# AFE_Shield.net
KiCad netlist of a schematic drawn in Altium Designer
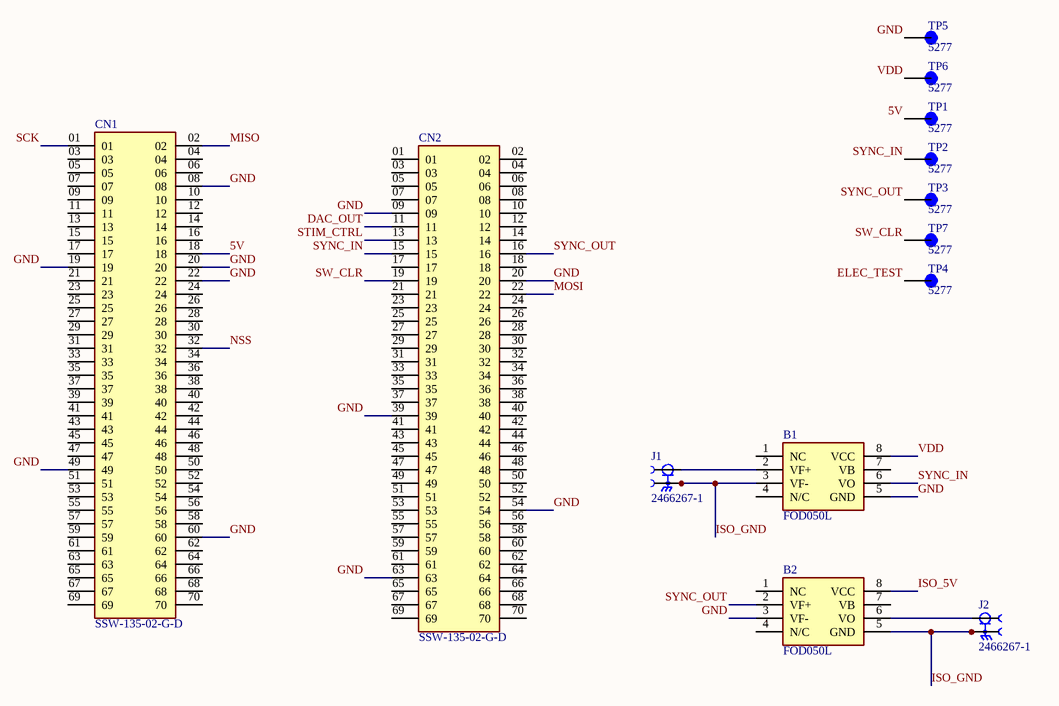
[diagram p0: AFE Shield.SchDoc]

(export (version "E")
  (design (tool "Eeschema 10.0.6"))
  (components
    (comp (ref "B1")
      (value "FOD050L")
      (footprint "SOIC127P594X363-8N")
      (fields (field (name "MOUSER PART NUMBER") "512-FOD050L"))
      (libsource (lib "James' Workspace") (part "FOD050L"))
    )
    (comp (ref "B2")
      (value "FOD050L")
      (footprint "SOIC127P594X363-8N")
      (fields (field (name "MOUSER PART NUMBER") "512-FOD050L"))
      (libsource (lib "James' Workspace") (part "FOD050L"))
    )
    (comp (ref "CN1")
      (value "SSW-135-02-G-D")
      (footprint "SAMTEC_SSW-135-02-G-D")
      (description "70-pin connector")
      (fields (field (name "MF") "Samtec"))
      (libsource (lib "James' Workspace") (part "SSW-135-02-G-D"))
    )
    (comp (ref "CN2")
      (value "SSW-135-02-G-D")
      (footprint "SAMTEC_SSW-135-02-G-D")
      (description "70-pin connector")
      (fields (field (name "MF") "Samtec"))
      (libsource (lib "James' Workspace") (part "SSW-135-02-G-D"))
    )
    (comp (ref "J1")
      (value "2466267-1")
      (footprint "TE_2466267-1")
      (description "BNC connector")
      (libsource (lib "") (part "2466267-1_1"))
    )
    (comp (ref "J2")
      (value "2466267-1")
      (footprint "TE_2466267-1")
      (description "BNC connector")
      (libsource (lib "James' Workspace") (part "2466267-1"))
    )
    (comp (ref "TP1")
      (value "5277")
      (footprint "KEYSTONE_5277")
      (description "TEST POINT (BLUE) - COMPACT")
      (fields (field (name "MF") "Keystone Electronics"))
      (libsource (lib "James' Workspace") (part "5277"))
    )
    (comp (ref "TP2")
      (value "5277")
      (footprint "KEYSTONE_5277")
      (description "TEST POINT (BLUE) - COMPACT")
      (fields (field (name "MF") "Keystone Electronics"))
      (libsource (lib "James' Workspace") (part "5277"))
    )
    (comp (ref "TP3")
      (value "5277")
      (footprint "KEYSTONE_5277")
      (description "TEST POINT (BLUE) - COMPACT")
      (fields (field (name "MF") "Keystone Electronics"))
      (libsource (lib "James' Workspace") (part "5277"))
    )
    (comp (ref "TP4")
      (value "5277")
      (footprint "KEYSTONE_5277")
      (description "TEST POINT (BLUE) - COMPACT")
      (fields (field (name "MF") "Keystone Electronics"))
      (libsource (lib "James' Workspace") (part "5277"))
    )
    (comp (ref "TP5")
      (value "5277")
      (footprint "KEYSTONE_5277")
      (description "TEST POINT (BLUE) - COMPACT")
      (fields (field (name "MF") "Keystone Electronics"))
      (libsource (lib "James' Workspace") (part "5277"))
    )
    (comp (ref "TP6")
      (value "5277")
      (footprint "KEYSTONE_5277")
      (description "TEST POINT (BLUE) - COMPACT")
      (fields (field (name "MF") "Keystone Electronics"))
      (libsource (lib "James' Workspace") (part "5277"))
    )
    (comp (ref "TP7")
      (value "5277")
      (footprint "KEYSTONE_5277")
      (description "TEST POINT (BLUE) - COMPACT")
      (fields (field (name "MF") "Keystone Electronics"))
      (libsource (lib "James' Workspace") (part "5277"))
    )
  )
  (nets
    (net (code "1") (name "/5V") (class "Default")
      (node (ref "CN1") (pin "18") (pinfunction "18_18") (pintype "passive"))
      (node (ref "TP1") (pin "1") (pinfunction "TP_1") (pintype "passive"))
    )
    (net (code "2") (name "/DAC_OUT") (class "Default")
      (node (ref "CN2") (pin "11") (pinfunction "11_11") (pintype "passive"))
    )
    (net (code "3") (name "/ELEC_TEST") (class "Default")
      (node (ref "TP4") (pin "1") (pinfunction "TP_1") (pintype "passive"))
    )
    (net (code "4") (name "/GND") (class "Default")
      (node (ref "B1") (pin "5") (pinfunction "GND_5") (pintype "passive"))
      (node (ref "B2") (pin "3") (pinfunction "VF-_3") (pintype "passive"))
      (node (ref "CN1") (pin "08") (pinfunction "08_08") (pintype "passive"))
      (node (ref "CN1") (pin "19") (pinfunction "19_19") (pintype "passive"))
      (node (ref "CN1") (pin "20") (pinfunction "20_20") (pintype "passive"))
      (node (ref "CN1") (pin "22") (pinfunction "22_22") (pintype "passive"))
      (node (ref "CN1") (pin "49") (pinfunction "49_49") (pintype "passive"))
      (node (ref "CN1") (pin "60") (pinfunction "60_60") (pintype "passive"))
      (node (ref "CN2") (pin "09") (pinfunction "09_09") (pintype "passive"))
      (node (ref "CN2") (pin "20") (pinfunction "20_20") (pintype "passive"))
      (node (ref "CN2") (pin "39") (pinfunction "39_39") (pintype "passive"))
      (node (ref "CN2") (pin "54") (pinfunction "54_54") (pintype "passive"))
      (node (ref "CN2") (pin "63") (pinfunction "63_63") (pintype "passive"))
      (node (ref "TP5") (pin "1") (pinfunction "TP_1") (pintype "passive"))
    )
    (net (code "5") (name "/ISO_5V") (class "Default")
      (node (ref "B2") (pin "8") (pinfunction "VCC_8") (pintype "passive"))
    )
    (net (code "6") (name "/ISO_GND") (class "Default")
      (node (ref "B1") (pin "3") (pinfunction "VF-_3") (pintype "passive"))
      (node (ref "B2") (pin "5") (pinfunction "GND_5") (pintype "passive"))
      (node (ref "J1") (pin "2") (pinfunction "SH_2") (pintype "power_in"))
      (node (ref "J1") (pin "3") (pinfunction "SH_3") (pintype "power_in"))
      (node (ref "J1") (pin "4") (pinfunction "SH_4") (pintype "power_in"))
      (node (ref "J1") (pin "5") (pinfunction "SH_5") (pintype "power_in"))
      (node (ref "J2") (pin "2") (pinfunction "SH_2") (pintype "power_in"))
      (node (ref "J2") (pin "3") (pinfunction "SH_3") (pintype "power_in"))
      (node (ref "J2") (pin "4") (pinfunction "SH_4") (pintype "power_in"))
      (node (ref "J2") (pin "5") (pinfunction "SH_5") (pintype "power_in"))
    )
    (net (code "7") (name "/MISO") (class "Default")
      (node (ref "CN1") (pin "02") (pinfunction "02_02") (pintype "passive"))
    )
    (net (code "8") (name "/MOSI") (class "Default")
      (node (ref "CN2") (pin "22") (pinfunction "22_22") (pintype "passive"))
    )
    (net (code "9") (name "/NSS") (class "Default")
      (node (ref "CN1") (pin "32") (pinfunction "32_32") (pintype "passive"))
    )
    (net (code "10") (name "/SCK") (class "Default")
      (node (ref "CN1") (pin "01") (pinfunction "01_01") (pintype "passive"))
    )
    (net (code "11") (name "/STIM_CTRL") (class "Default")
      (node (ref "CN2") (pin "13") (pinfunction "13_13") (pintype "passive"))
    )
    (net (code "12") (name "/SW_CLR") (class "Default")
      (node (ref "CN2") (pin "19") (pinfunction "19_19") (pintype "passive"))
      (node (ref "TP7") (pin "1") (pinfunction "TP_1") (pintype "passive"))
    )
    (net (code "13") (name "/SYNC_IN") (class "Default")
      (node (ref "B1") (pin "6") (pinfunction "VO_6") (pintype "passive"))
      (node (ref "CN2") (pin "15") (pinfunction "15_15") (pintype "passive"))
      (node (ref "TP2") (pin "1") (pinfunction "TP_1") (pintype "passive"))
    )
    (net (code "14") (name "/SYNC_OUT") (class "Default")
      (node (ref "B2") (pin "2") (pinfunction "VF+_2") (pintype "passive"))
      (node (ref "CN2") (pin "16") (pinfunction "16_16") (pintype "passive"))
      (node (ref "TP3") (pin "1") (pinfunction "TP_1") (pintype "passive"))
    )
    (net (code "15") (name "/VDD") (class "Default")
      (node (ref "B1") (pin "8") (pinfunction "VCC_8") (pintype "passive"))
      (node (ref "TP6") (pin "1") (pinfunction "TP_1") (pintype "passive"))
    )
    (net (code "16") (name "Net-(B1-VF+)") (class "Default")
      (node (ref "B1") (pin "2") (pinfunction "VF+_2") (pintype "passive"))
      (node (ref "J1") (pin "1") (pinfunction "SIG_1") (pintype "passive"))
    )
    (net (code "17") (name "Net-(B2-VO)") (class "Default")
      (node (ref "B2") (pin "6") (pinfunction "VO_6") (pintype "passive"))
      (node (ref "J2") (pin "1") (pinfunction "SIG_1") (pintype "passive"))
    )
    (net (code "18") (name "unconnected-(B1-NC-Pad1)") (class "Default")
      (node (ref "B1") (pin "1") (pinfunction "NC_1") (pintype "passive"))
    )
    (net (code "19") (name "unconnected-(B1-N{slash}C-Pad4)") (class "Default")
      (node (ref "B1") (pin "4") (pinfunction "N/C_4") (pintype "passive"))
    )
    (net (code "20") (name "unconnected-(B1-VB-Pad7)") (class "Default")
      (node (ref "B1") (pin "7") (pinfunction "VB_7") (pintype "passive"))
    )
    (net (code "21") (name "unconnected-(B2-NC-Pad1)") (class "Default")
      (node (ref "B2") (pin "1") (pinfunction "NC_1") (pintype "passive"))
    )
    (net (code "22") (name "unconnected-(B2-N{slash}C-Pad4)") (class "Default")
      (node (ref "B2") (pin "4") (pinfunction "N/C_4") (pintype "passive"))
    )
    (net (code "23") (name "unconnected-(B2-VB-Pad7)") (class "Default")
      (node (ref "B2") (pin "7") (pinfunction "VB_7") (pintype "passive"))
    )
    (net (code "24") (name "unconnected-(CN1-Pad03)") (class "Default")
      (node (ref "CN1") (pin "03") (pinfunction "03_03") (pintype "passive"))
    )
    (net (code "25") (name "unconnected-(CN1-Pad04)") (class "Default")
      (node (ref "CN1") (pin "04") (pinfunction "04_04") (pintype "passive"))
    )
    (net (code "26") (name "unconnected-(CN1-Pad05)") (class "Default")
      (node (ref "CN1") (pin "05") (pinfunction "05_05") (pintype "passive"))
    )
    (net (code "27") (name "unconnected-(CN1-Pad06)") (class "Default")
      (node (ref "CN1") (pin "06") (pinfunction "06_06") (pintype "passive"))
    )
    (net (code "28") (name "unconnected-(CN1-Pad07)") (class "Default")
      (node (ref "CN1") (pin "07") (pinfunction "07_07") (pintype "passive"))
    )
    (net (code "29") (name "unconnected-(CN1-Pad09)") (class "Default")
      (node (ref "CN1") (pin "09") (pinfunction "09_09") (pintype "passive"))
    )
    (net (code "30") (name "unconnected-(CN1-Pad10)") (class "Default")
      (node (ref "CN1") (pin "10") (pinfunction "10_10") (pintype "passive"))
    )
    (net (code "31") (name "unconnected-(CN1-Pad11)") (class "Default")
      (node (ref "CN1") (pin "11") (pinfunction "11_11") (pintype "passive"))
    )
    (net (code "32") (name "unconnected-(CN1-Pad12)") (class "Default")
      (node (ref "CN1") (pin "12") (pinfunction "12_12") (pintype "passive"))
    )
    (net (code "33") (name "unconnected-(CN1-Pad13)") (class "Default")
      (node (ref "CN1") (pin "13") (pinfunction "13_13") (pintype "passive"))
    )
    (net (code "34") (name "unconnected-(CN1-Pad14)") (class "Default")
      (node (ref "CN1") (pin "14") (pinfunction "14_14") (pintype "passive"))
    )
    (net (code "35") (name "unconnected-(CN1-Pad15)") (class "Default")
      (node (ref "CN1") (pin "15") (pinfunction "15_15") (pintype "passive"))
    )
    (net (code "36") (name "unconnected-(CN1-Pad16)") (class "Default")
      (node (ref "CN1") (pin "16") (pinfunction "16_16") (pintype "passive"))
    )
    (net (code "37") (name "unconnected-(CN1-Pad17)") (class "Default")
      (node (ref "CN1") (pin "17") (pinfunction "17_17") (pintype "passive"))
    )
    (net (code "38") (name "unconnected-(CN1-Pad21)") (class "Default")
      (node (ref "CN1") (pin "21") (pinfunction "21_21") (pintype "passive"))
    )
    (net (code "39") (name "unconnected-(CN1-Pad23)") (class "Default")
      (node (ref "CN1") (pin "23") (pinfunction "23_23") (pintype "passive"))
    )
    (net (code "40") (name "unconnected-(CN1-Pad24)") (class "Default")
      (node (ref "CN1") (pin "24") (pinfunction "24_24") (pintype "passive"))
    )
    (net (code "41") (name "unconnected-(CN1-Pad25)") (class "Default")
      (node (ref "CN1") (pin "25") (pinfunction "25_25") (pintype "passive"))
    )
    (net (code "42") (name "unconnected-(CN1-Pad26)") (class "Default")
      (node (ref "CN1") (pin "26") (pinfunction "26_26") (pintype "passive"))
    )
    (net (code "43") (name "unconnected-(CN1-Pad27)") (class "Default")
      (node (ref "CN1") (pin "27") (pinfunction "27_27") (pintype "passive"))
    )
    (net (code "44") (name "unconnected-(CN1-Pad28)") (class "Default")
      (node (ref "CN1") (pin "28") (pinfunction "28_28") (pintype "passive"))
    )
    (net (code "45") (name "unconnected-(CN1-Pad29)") (class "Default")
      (node (ref "CN1") (pin "29") (pinfunction "29_29") (pintype "passive"))
    )
    (net (code "46") (name "unconnected-(CN1-Pad30)") (class "Default")
      (node (ref "CN1") (pin "30") (pinfunction "30_30") (pintype "passive"))
    )
    (net (code "47") (name "unconnected-(CN1-Pad31)") (class "Default")
      (node (ref "CN1") (pin "31") (pinfunction "31_31") (pintype "passive"))
    )
    (net (code "48") (name "unconnected-(CN1-Pad33)") (class "Default")
      (node (ref "CN1") (pin "33") (pinfunction "33_33") (pintype "passive"))
    )
    (net (code "49") (name "unconnected-(CN1-Pad34)") (class "Default")
      (node (ref "CN1") (pin "34") (pinfunction "34_34") (pintype "passive"))
    )
    (net (code "50") (name "unconnected-(CN1-Pad35)") (class "Default")
      (node (ref "CN1") (pin "35") (pinfunction "35_35") (pintype "passive"))
    )
    (net (code "51") (name "unconnected-(CN1-Pad36)") (class "Default")
      (node (ref "CN1") (pin "36") (pinfunction "36_36") (pintype "passive"))
    )
    (net (code "52") (name "unconnected-(CN1-Pad37)") (class "Default")
      (node (ref "CN1") (pin "37") (pinfunction "37_37") (pintype "passive"))
    )
    (net (code "53") (name "unconnected-(CN1-Pad38)") (class "Default")
      (node (ref "CN1") (pin "38") (pinfunction "38_38") (pintype "passive"))
    )
    (net (code "54") (name "unconnected-(CN1-Pad39)") (class "Default")
      (node (ref "CN1") (pin "39") (pinfunction "39_39") (pintype "passive"))
    )
    (net (code "55") (name "unconnected-(CN1-Pad40)") (class "Default")
      (node (ref "CN1") (pin "40") (pinfunction "40_40") (pintype "passive"))
    )
    (net (code "56") (name "unconnected-(CN1-Pad41)") (class "Default")
      (node (ref "CN1") (pin "41") (pinfunction "41_41") (pintype "passive"))
    )
    (net (code "57") (name "unconnected-(CN1-Pad42)") (class "Default")
      (node (ref "CN1") (pin "42") (pinfunction "42_42") (pintype "passive"))
    )
    (net (code "58") (name "unconnected-(CN1-Pad43)") (class "Default")
      (node (ref "CN1") (pin "43") (pinfunction "43_43") (pintype "passive"))
    )
    (net (code "59") (name "unconnected-(CN1-Pad44)") (class "Default")
      (node (ref "CN1") (pin "44") (pinfunction "44_44") (pintype "passive"))
    )
    (net (code "60") (name "unconnected-(CN1-Pad45)") (class "Default")
      (node (ref "CN1") (pin "45") (pinfunction "45_45") (pintype "passive"))
    )
    (net (code "61") (name "unconnected-(CN1-Pad46)") (class "Default")
      (node (ref "CN1") (pin "46") (pinfunction "46_46") (pintype "passive"))
    )
    (net (code "62") (name "unconnected-(CN1-Pad47)") (class "Default")
      (node (ref "CN1") (pin "47") (pinfunction "47_47") (pintype "passive"))
    )
    (net (code "63") (name "unconnected-(CN1-Pad48)") (class "Default")
      (node (ref "CN1") (pin "48") (pinfunction "48_48") (pintype "passive"))
    )
    (net (code "64") (name "unconnected-(CN1-Pad50)") (class "Default")
      (node (ref "CN1") (pin "50") (pinfunction "50_50") (pintype "passive"))
    )
    (net (code "65") (name "unconnected-(CN1-Pad51)") (class "Default")
      (node (ref "CN1") (pin "51") (pinfunction "51_51") (pintype "passive"))
    )
    (net (code "66") (name "unconnected-(CN1-Pad52)") (class "Default")
      (node (ref "CN1") (pin "52") (pinfunction "52_52") (pintype "passive"))
    )
    (net (code "67") (name "unconnected-(CN1-Pad53)") (class "Default")
      (node (ref "CN1") (pin "53") (pinfunction "53_53") (pintype "passive"))
    )
    (net (code "68") (name "unconnected-(CN1-Pad54)") (class "Default")
      (node (ref "CN1") (pin "54") (pinfunction "54_54") (pintype "passive"))
    )
    (net (code "69") (name "unconnected-(CN1-Pad55)") (class "Default")
      (node (ref "CN1") (pin "55") (pinfunction "55_55") (pintype "passive"))
    )
    (net (code "70") (name "unconnected-(CN1-Pad56)") (class "Default")
      (node (ref "CN1") (pin "56") (pinfunction "56_56") (pintype "passive"))
    )
    (net (code "71") (name "unconnected-(CN1-Pad57)") (class "Default")
      (node (ref "CN1") (pin "57") (pinfunction "57_57") (pintype "passive"))
    )
    (net (code "72") (name "unconnected-(CN1-Pad58)") (class "Default")
      (node (ref "CN1") (pin "58") (pinfunction "58_58") (pintype "passive"))
    )
    (net (code "73") (name "unconnected-(CN1-Pad59)") (class "Default")
      (node (ref "CN1") (pin "59") (pinfunction "59_59") (pintype "passive"))
    )
    (net (code "74") (name "unconnected-(CN1-Pad61)") (class "Default")
      (node (ref "CN1") (pin "61") (pinfunction "61_61") (pintype "passive"))
    )
    (net (code "75") (name "unconnected-(CN1-Pad62)") (class "Default")
      (node (ref "CN1") (pin "62") (pinfunction "62_62") (pintype "passive"))
    )
    (net (code "76") (name "unconnected-(CN1-Pad63)") (class "Default")
      (node (ref "CN1") (pin "63") (pinfunction "63_63") (pintype "passive"))
    )
    (net (code "77") (name "unconnected-(CN1-Pad64)") (class "Default")
      (node (ref "CN1") (pin "64") (pinfunction "64_64") (pintype "passive"))
    )
    (net (code "78") (name "unconnected-(CN1-Pad65)") (class "Default")
      (node (ref "CN1") (pin "65") (pinfunction "65_65") (pintype "passive"))
    )
    (net (code "79") (name "unconnected-(CN1-Pad66)") (class "Default")
      (node (ref "CN1") (pin "66") (pinfunction "66_66") (pintype "passive"))
    )
    (net (code "80") (name "unconnected-(CN1-Pad67)") (class "Default")
      (node (ref "CN1") (pin "67") (pinfunction "67_67") (pintype "passive"))
    )
    (net (code "81") (name "unconnected-(CN1-Pad68)") (class "Default")
      (node (ref "CN1") (pin "68") (pinfunction "68_68") (pintype "passive"))
    )
    (net (code "82") (name "unconnected-(CN1-Pad69)") (class "Default")
      (node (ref "CN1") (pin "69") (pinfunction "69_69") (pintype "passive"))
    )
    (net (code "83") (name "unconnected-(CN1-Pad70)") (class "Default")
      (node (ref "CN1") (pin "70") (pinfunction "70_70") (pintype "passive"))
    )
    (net (code "84") (name "unconnected-(CN2-Pad01)") (class "Default")
      (node (ref "CN2") (pin "01") (pinfunction "01_01") (pintype "passive"))
    )
    (net (code "85") (name "unconnected-(CN2-Pad02)") (class "Default")
      (node (ref "CN2") (pin "02") (pinfunction "02_02") (pintype "passive"))
    )
    (net (code "86") (name "unconnected-(CN2-Pad03)") (class "Default")
      (node (ref "CN2") (pin "03") (pinfunction "03_03") (pintype "passive"))
    )
    (net (code "87") (name "unconnected-(CN2-Pad04)") (class "Default")
      (node (ref "CN2") (pin "04") (pinfunction "04_04") (pintype "passive"))
    )
    (net (code "88") (name "unconnected-(CN2-Pad05)") (class "Default")
      (node (ref "CN2") (pin "05") (pinfunction "05_05") (pintype "passive"))
    )
    (net (code "89") (name "unconnected-(CN2-Pad06)") (class "Default")
      (node (ref "CN2") (pin "06") (pinfunction "06_06") (pintype "passive"))
    )
    (net (code "90") (name "unconnected-(CN2-Pad07)") (class "Default")
      (node (ref "CN2") (pin "07") (pinfunction "07_07") (pintype "passive"))
    )
    (net (code "91") (name "unconnected-(CN2-Pad08)") (class "Default")
      (node (ref "CN2") (pin "08") (pinfunction "08_08") (pintype "passive"))
    )
    (net (code "92") (name "unconnected-(CN2-Pad10)") (class "Default")
      (node (ref "CN2") (pin "10") (pinfunction "10_10") (pintype "passive"))
    )
    (net (code "93") (name "unconnected-(CN2-Pad12)") (class "Default")
      (node (ref "CN2") (pin "12") (pinfunction "12_12") (pintype "passive"))
    )
    (net (code "94") (name "unconnected-(CN2-Pad14)") (class "Default")
      (node (ref "CN2") (pin "14") (pinfunction "14_14") (pintype "passive"))
    )
    (net (code "95") (name "unconnected-(CN2-Pad17)") (class "Default")
      (node (ref "CN2") (pin "17") (pinfunction "17_17") (pintype "passive"))
    )
    (net (code "96") (name "unconnected-(CN2-Pad18)") (class "Default")
      (node (ref "CN2") (pin "18") (pinfunction "18_18") (pintype "passive"))
    )
    (net (code "97") (name "unconnected-(CN2-Pad21)") (class "Default")
      (node (ref "CN2") (pin "21") (pinfunction "21_21") (pintype "passive"))
    )
    (net (code "98") (name "unconnected-(CN2-Pad23)") (class "Default")
      (node (ref "CN2") (pin "23") (pinfunction "23_23") (pintype "passive"))
    )
    (net (code "99") (name "unconnected-(CN2-Pad24)") (class "Default")
      (node (ref "CN2") (pin "24") (pinfunction "24_24") (pintype "passive"))
    )
    (net (code "100") (name "unconnected-(CN2-Pad25)") (class "Default")
      (node (ref "CN2") (pin "25") (pinfunction "25_25") (pintype "passive"))
    )
    (net (code "101") (name "unconnected-(CN2-Pad26)") (class "Default")
      (node (ref "CN2") (pin "26") (pinfunction "26_26") (pintype "passive"))
    )
    (net (code "102") (name "unconnected-(CN2-Pad27)") (class "Default")
      (node (ref "CN2") (pin "27") (pinfunction "27_27") (pintype "passive"))
    )
    (net (code "103") (name "unconnected-(CN2-Pad28)") (class "Default")
      (node (ref "CN2") (pin "28") (pinfunction "28_28") (pintype "passive"))
    )
    (net (code "104") (name "unconnected-(CN2-Pad29)") (class "Default")
      (node (ref "CN2") (pin "29") (pinfunction "29_29") (pintype "passive"))
    )
    (net (code "105") (name "unconnected-(CN2-Pad30)") (class "Default")
      (node (ref "CN2") (pin "30") (pinfunction "30_30") (pintype "passive"))
    )
    (net (code "106") (name "unconnected-(CN2-Pad31)") (class "Default")
      (node (ref "CN2") (pin "31") (pinfunction "31_31") (pintype "passive"))
    )
    (net (code "107") (name "unconnected-(CN2-Pad32)") (class "Default")
      (node (ref "CN2") (pin "32") (pinfunction "32_32") (pintype "passive"))
    )
    (net (code "108") (name "unconnected-(CN2-Pad33)") (class "Default")
      (node (ref "CN2") (pin "33") (pinfunction "33_33") (pintype "passive"))
    )
    (net (code "109") (name "unconnected-(CN2-Pad34)") (class "Default")
      (node (ref "CN2") (pin "34") (pinfunction "34_34") (pintype "passive"))
    )
    (net (code "110") (name "unconnected-(CN2-Pad35)") (class "Default")
      (node (ref "CN2") (pin "35") (pinfunction "35_35") (pintype "passive"))
    )
    (net (code "111") (name "unconnected-(CN2-Pad36)") (class "Default")
      (node (ref "CN2") (pin "36") (pinfunction "36_36") (pintype "passive"))
    )
    (net (code "112") (name "unconnected-(CN2-Pad37)") (class "Default")
      (node (ref "CN2") (pin "37") (pinfunction "37_37") (pintype "passive"))
    )
    (net (code "113") (name "unconnected-(CN2-Pad38)") (class "Default")
      (node (ref "CN2") (pin "38") (pinfunction "38_38") (pintype "passive"))
    )
    (net (code "114") (name "unconnected-(CN2-Pad40)") (class "Default")
      (node (ref "CN2") (pin "40") (pinfunction "40_40") (pintype "passive"))
    )
    (net (code "115") (name "unconnected-(CN2-Pad41)") (class "Default")
      (node (ref "CN2") (pin "41") (pinfunction "41_41") (pintype "passive"))
    )
    (net (code "116") (name "unconnected-(CN2-Pad42)") (class "Default")
      (node (ref "CN2") (pin "42") (pinfunction "42_42") (pintype "passive"))
    )
    (net (code "117") (name "unconnected-(CN2-Pad43)") (class "Default")
      (node (ref "CN2") (pin "43") (pinfunction "43_43") (pintype "passive"))
    )
    (net (code "118") (name "unconnected-(CN2-Pad44)") (class "Default")
      (node (ref "CN2") (pin "44") (pinfunction "44_44") (pintype "passive"))
    )
    (net (code "119") (name "unconnected-(CN2-Pad45)") (class "Default")
      (node (ref "CN2") (pin "45") (pinfunction "45_45") (pintype "passive"))
    )
    (net (code "120") (name "unconnected-(CN2-Pad46)") (class "Default")
      (node (ref "CN2") (pin "46") (pinfunction "46_46") (pintype "passive"))
    )
    (net (code "121") (name "unconnected-(CN2-Pad47)") (class "Default")
      (node (ref "CN2") (pin "47") (pinfunction "47_47") (pintype "passive"))
    )
    (net (code "122") (name "unconnected-(CN2-Pad48)") (class "Default")
      (node (ref "CN2") (pin "48") (pinfunction "48_48") (pintype "passive"))
    )
    (net (code "123") (name "unconnected-(CN2-Pad49)") (class "Default")
      (node (ref "CN2") (pin "49") (pinfunction "49_49") (pintype "passive"))
    )
    (net (code "124") (name "unconnected-(CN2-Pad50)") (class "Default")
      (node (ref "CN2") (pin "50") (pinfunction "50_50") (pintype "passive"))
    )
    (net (code "125") (name "unconnected-(CN2-Pad51)") (class "Default")
      (node (ref "CN2") (pin "51") (pinfunction "51_51") (pintype "passive"))
    )
    (net (code "126") (name "unconnected-(CN2-Pad52)") (class "Default")
      (node (ref "CN2") (pin "52") (pinfunction "52_52") (pintype "passive"))
    )
    (net (code "127") (name "unconnected-(CN2-Pad53)") (class "Default")
      (node (ref "CN2") (pin "53") (pinfunction "53_53") (pintype "passive"))
    )
    (net (code "128") (name "unconnected-(CN2-Pad55)") (class "Default")
      (node (ref "CN2") (pin "55") (pinfunction "55_55") (pintype "passive"))
    )
    (net (code "129") (name "unconnected-(CN2-Pad56)") (class "Default")
      (node (ref "CN2") (pin "56") (pinfunction "56_56") (pintype "passive"))
    )
    (net (code "130") (name "unconnected-(CN2-Pad57)") (class "Default")
      (node (ref "CN2") (pin "57") (pinfunction "57_57") (pintype "passive"))
    )
    (net (code "131") (name "unconnected-(CN2-Pad58)") (class "Default")
      (node (ref "CN2") (pin "58") (pinfunction "58_58") (pintype "passive"))
    )
    (net (code "132") (name "unconnected-(CN2-Pad59)") (class "Default")
      (node (ref "CN2") (pin "59") (pinfunction "59_59") (pintype "passive"))
    )
    (net (code "133") (name "unconnected-(CN2-Pad60)") (class "Default")
      (node (ref "CN2") (pin "60") (pinfunction "60_60") (pintype "passive"))
    )
    (net (code "134") (name "unconnected-(CN2-Pad61)") (class "Default")
      (node (ref "CN2") (pin "61") (pinfunction "61_61") (pintype "passive"))
    )
    (net (code "135") (name "unconnected-(CN2-Pad62)") (class "Default")
      (node (ref "CN2") (pin "62") (pinfunction "62_62") (pintype "passive"))
    )
    (net (code "136") (name "unconnected-(CN2-Pad64)") (class "Default")
      (node (ref "CN2") (pin "64") (pinfunction "64_64") (pintype "passive"))
    )
    (net (code "137") (name "unconnected-(CN2-Pad65)") (class "Default")
      (node (ref "CN2") (pin "65") (pinfunction "65_65") (pintype "passive"))
    )
    (net (code "138") (name "unconnected-(CN2-Pad66)") (class "Default")
      (node (ref "CN2") (pin "66") (pinfunction "66_66") (pintype "passive"))
    )
    (net (code "139") (name "unconnected-(CN2-Pad67)") (class "Default")
      (node (ref "CN2") (pin "67") (pinfunction "67_67") (pintype "passive"))
    )
    (net (code "140") (name "unconnected-(CN2-Pad68)") (class "Default")
      (node (ref "CN2") (pin "68") (pinfunction "68_68") (pintype "passive"))
    )
    (net (code "141") (name "unconnected-(CN2-Pad69)") (class "Default")
      (node (ref "CN2") (pin "69") (pinfunction "69_69") (pintype "passive"))
    )
    (net (code "142") (name "unconnected-(CN2-Pad70)") (class "Default")
      (node (ref "CN2") (pin "70") (pinfunction "70_70") (pintype "passive"))
    )
  )
)
